# V4-AddOnESP32-V02-011.net
KiCad netlist of a schematic drawn in EAGLE
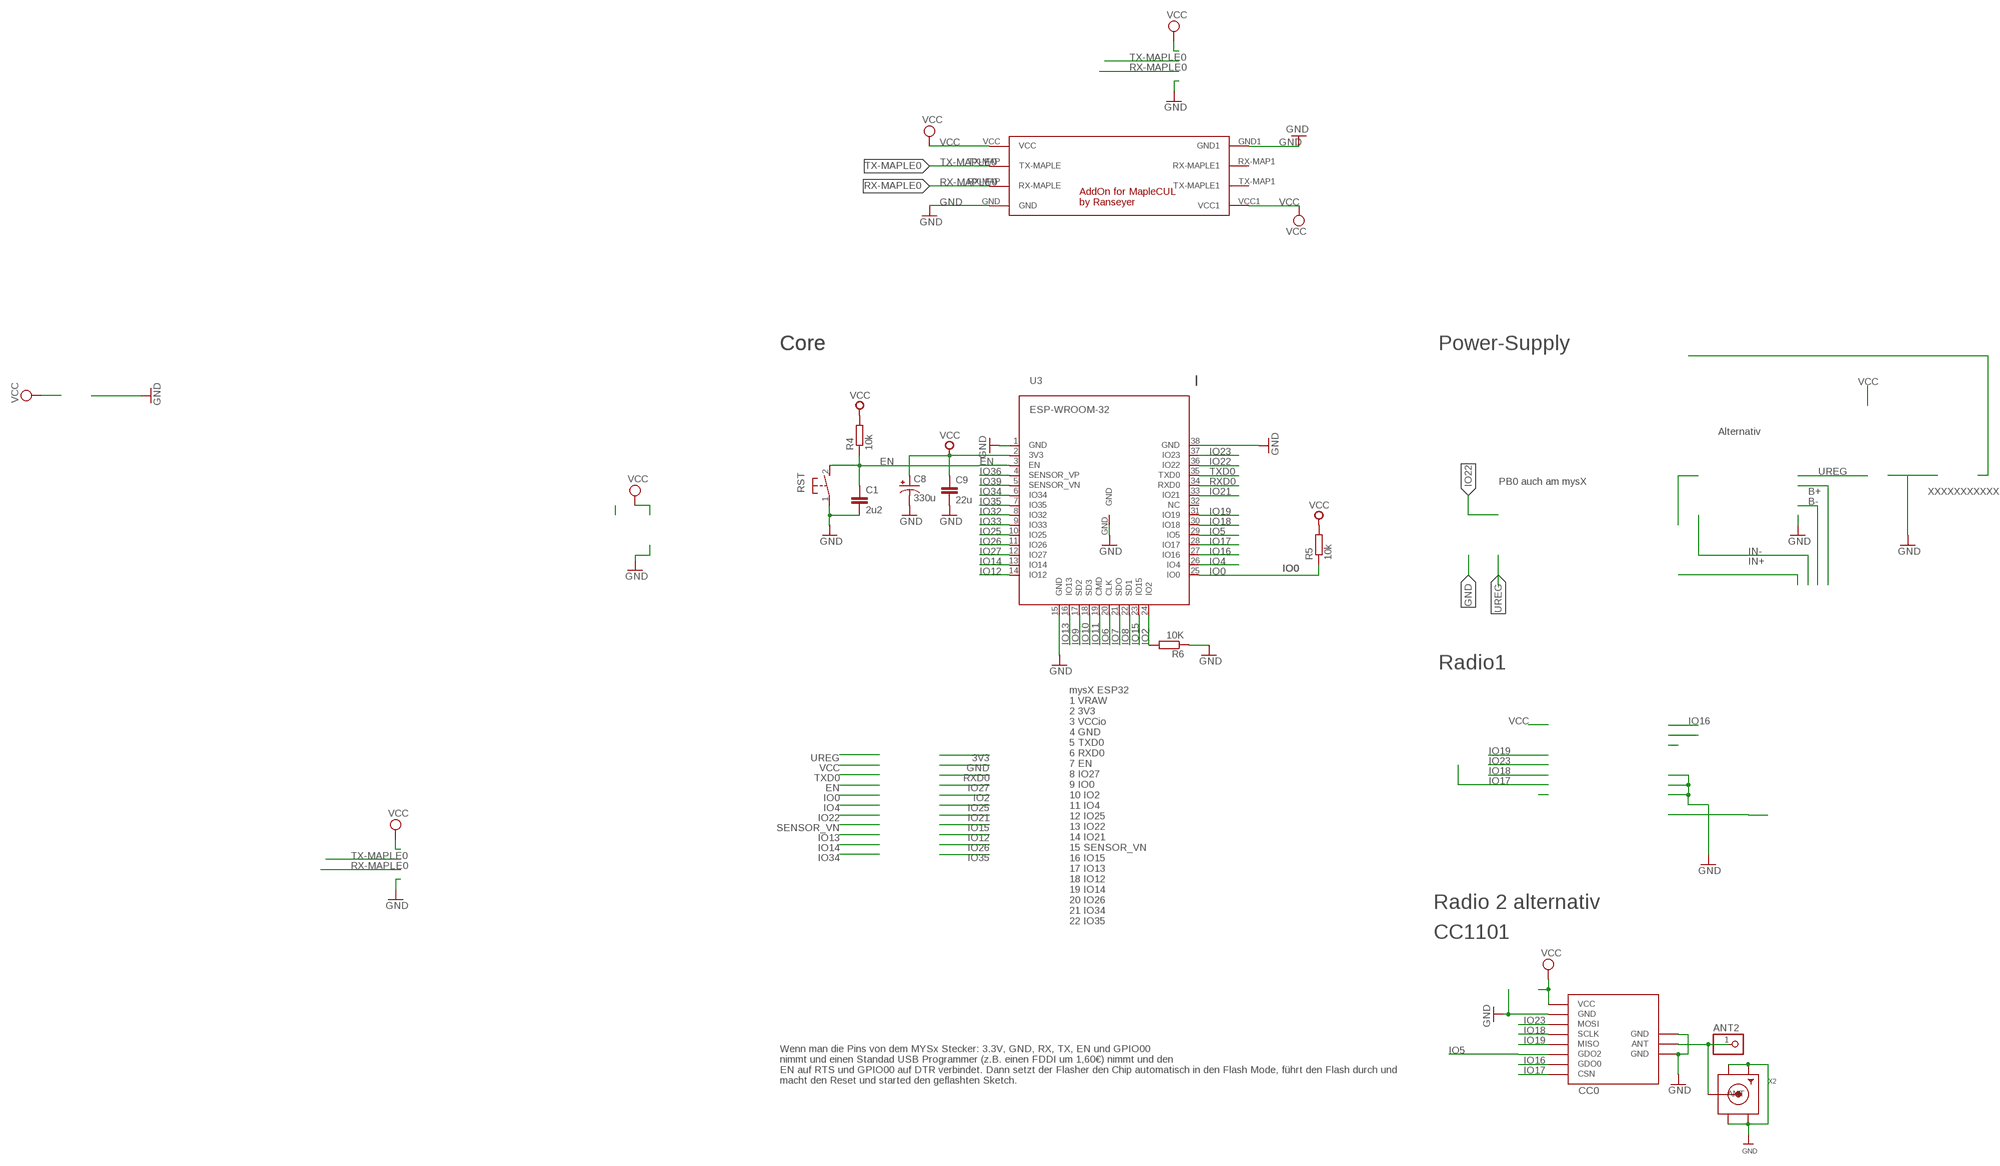
[diagram p0: schematic, sheet 1]

(export (version "E")
  (design (tool "Eeschema 10.0.6"))
  (components
    (comp (ref "ANT2")
      (value "PINHD-1X1")
      (footprint "eagle-import:1X01")
      (libsource (lib "eagle-import") (part "PINHD-1X1"))
    )
    (comp (ref "C1")
      (value "2u2")
      (footprint "eagle-import:C0805")
      (libsource (lib "eagle-import") (part "C-EUC0805"))
    )
    (comp (ref "C8")
      (value "330u")
      (footprint "eagle-import:VISHAY_C")
      (libsource (lib "eagle-import") (part "CAP_POLSMD"))
    )
    (comp (ref "C9")
      (value "22u")
      (footprint "eagle-import:C0805")
      (libsource (lib "eagle-import") (part "C-EUC0805"))
    )
    (comp (ref "CC0")
      (value "CC1101")
      (footprint "eagle-import:CC1101_MODULE1_SMD")
      (libsource (lib "eagle-import") (part "CC1101_MODULE1SMD"))
    )
    (comp (ref "R4")
      (value "10k")
      (footprint "eagle-import:M0805")
      (libsource (lib "eagle-import") (part "rcl@1_R-EU_M0805"))
    )
    (comp (ref "R5")
      (value "10k")
      (footprint "eagle-import:M0805")
      (libsource (lib "eagle-import") (part "rcl_334_R-EU_M0805"))
    )
    (comp (ref "R6")
      (value "10K")
      (footprint "eagle-import:M0805")
      (libsource (lib "eagle-import") (part "R-EU_M0805"))
    )
    (comp (ref "RST")
      (value "DTSM-3")
      (footprint "eagle-import:DTSM-3")
      (libsource (lib "eagle-import") (part "DTSM-3"))
    )
    (comp (ref "U$2")
      (value "MAPLE-CUL-ADDON-V01")
      (footprint "eagle-import:MAPLE-CUL-V01")
      (libsource (lib "eagle-import") (part "MAPLE-CUL-ADDON-V01"))
    )
    (comp (ref "U3")
      (value "ESP-WROOM-32")
      (footprint "eagle-import:ESP-WROOM-32")
      (libsource (lib "eagle-import") (part "ESP-WROOM-32"))
    )
    (comp (ref "X2")
      (value "SMACONNECTOR_EDGE")
      (footprint "eagle-import:SMA_EDGELAUNCH")
      (libsource (lib "eagle-import") (part "SMACONNECTOR_EDGE"))
    )
  )
  (nets
    (net (code "4") (name "/EN") (class "Default")
      (node (ref "C1") (pin "1") (pinfunction "1_1") (pintype "passive"))
      (node (ref "R4") (pin "1") (pinfunction "1_1") (pintype "passive"))
      (node (ref "RST") (pin "2") (pinfunction "2_2") (pintype "passive"))
      (node (ref "U3") (pin "3") (pinfunction "EN_3") (pintype "bidirectional"))
    )
    (net (code "7") (name "/IO0") (class "Default")
      (node (ref "R5") (pin "1") (pinfunction "1_1") (pintype "passive"))
      (node (ref "U3") (pin "25") (pinfunction "IO0_25") (pintype "bidirectional"))
    )
    (net (code "8") (name "/IO2") (class "Default")
      (node (ref "R6") (pin "2") (pinfunction "2_2") (pintype "passive"))
      (node (ref "U3") (pin "24") (pinfunction "IO2_24") (pintype "bidirectional"))
    )
    (net (code "9") (name "/IO4") (class "Default")
      (node (ref "U3") (pin "26") (pinfunction "IO4_26") (pintype "bidirectional"))
    )
    (net (code "10") (name "/IO5") (class "Default")
      (node (ref "CC0") (pin "GDO2") (pinfunction "GDO2_GDO2") (pintype "bidirectional"))
      (node (ref "U3") (pin "29") (pinfunction "IO5_29") (pintype "bidirectional"))
    )
    (net (code "11") (name "/IO6") (class "Default")
      (node (ref "U3") (pin "20") (pinfunction "CLK_20") (pintype "bidirectional"))
    )
    (net (code "12") (name "/IO7") (class "Default")
      (node (ref "U3") (pin "21") (pinfunction "SDO_21") (pintype "bidirectional"))
    )
    (net (code "13") (name "/IO8") (class "Default")
      (node (ref "U3") (pin "22") (pinfunction "SD1_22") (pintype "bidirectional"))
    )
    (net (code "14") (name "/IO9") (class "Default")
      (node (ref "U3") (pin "17") (pinfunction "SD2_17") (pintype "bidirectional"))
    )
    (net (code "15") (name "/IO10") (class "Default")
      (node (ref "U3") (pin "18") (pinfunction "SD3_18") (pintype "bidirectional"))
    )
    (net (code "16") (name "/IO11") (class "Default")
      (node (ref "U3") (pin "19") (pinfunction "CMD_19") (pintype "bidirectional"))
    )
    (net (code "17") (name "/IO12") (class "Default")
      (node (ref "U3") (pin "14") (pinfunction "IO12_14") (pintype "bidirectional"))
    )
    (net (code "18") (name "/IO13") (class "Default")
      (node (ref "U3") (pin "16") (pinfunction "IO13_16") (pintype "bidirectional"))
    )
    (net (code "19") (name "/IO14") (class "Default")
      (node (ref "U3") (pin "13") (pinfunction "IO14_13") (pintype "bidirectional"))
    )
    (net (code "20") (name "/IO15") (class "Default")
      (node (ref "U3") (pin "23") (pinfunction "IO15_23") (pintype "bidirectional"))
    )
    (net (code "21") (name "/IO16") (class "Default")
      (node (ref "CC0") (pin "GDO0") (pinfunction "GDO0_GDO0") (pintype "bidirectional"))
      (node (ref "U3") (pin "27") (pinfunction "IO16_27") (pintype "bidirectional"))
    )
    (net (code "22") (name "/IO17") (class "Default")
      (node (ref "CC0") (pin "CSN") (pinfunction "CSN_CSN") (pintype "bidirectional"))
      (node (ref "U3") (pin "28") (pinfunction "IO17_28") (pintype "bidirectional"))
    )
    (net (code "23") (name "/IO18") (class "Default")
      (node (ref "CC0") (pin "SCLK") (pinfunction "SCLK_SCLK") (pintype "bidirectional"))
      (node (ref "U3") (pin "30") (pinfunction "IO18_30") (pintype "bidirectional"))
    )
    (net (code "24") (name "/IO19") (class "Default")
      (node (ref "CC0") (pin "MISO") (pinfunction "MISO_MISO") (pintype "bidirectional"))
      (node (ref "U3") (pin "31") (pinfunction "IO19_31") (pintype "bidirectional"))
    )
    (net (code "25") (name "/IO21") (class "Default")
      (node (ref "U3") (pin "33") (pinfunction "IO21_33") (pintype "bidirectional"))
    )
    (net (code "26") (name "/IO23") (class "Default")
      (node (ref "CC0") (pin "MOSI") (pinfunction "MOSI_MOSI") (pintype "bidirectional"))
      (node (ref "U3") (pin "37") (pinfunction "IO23_37") (pintype "bidirectional"))
    )
    (net (code "27") (name "/IO25") (class "Default")
      (node (ref "U3") (pin "10") (pinfunction "IO25_10") (pintype "bidirectional"))
    )
    (net (code "28") (name "/IO26") (class "Default")
      (node (ref "U3") (pin "11") (pinfunction "IO26_11") (pintype "bidirectional"))
    )
    (net (code "29") (name "/IO27") (class "Default")
      (node (ref "U3") (pin "12") (pinfunction "IO27_12") (pintype "bidirectional"))
    )
    (net (code "30") (name "/IO32") (class "Default")
      (node (ref "U3") (pin "8") (pinfunction "IO32_8") (pintype "bidirectional"))
    )
    (net (code "31") (name "/IO33") (class "Default")
      (node (ref "U3") (pin "9") (pinfunction "IO33_9") (pintype "bidirectional"))
    )
    (net (code "32") (name "/IO34") (class "Default")
      (node (ref "U3") (pin "6") (pinfunction "IO34_6") (pintype "bidirectional"))
    )
    (net (code "33") (name "/IO35") (class "Default")
      (node (ref "U3") (pin "7") (pinfunction "IO35_7") (pintype "bidirectional"))
    )
    (net (code "34") (name "/IO36") (class "Default")
      (node (ref "U3") (pin "4") (pinfunction "SENSOR_VP_4") (pintype "bidirectional"))
    )
    (net (code "35") (name "/IO39") (class "Default")
      (node (ref "U3") (pin "5") (pinfunction "SENSOR_VN_5") (pintype "bidirectional"))
    )
    (net (code "36") (name "/RXD0") (class "Default")
      (node (ref "U3") (pin "34") (pinfunction "RXD0_34") (pintype "bidirectional"))
    )
    (net (code "38") (name "/TXD0") (class "Default")
      (node (ref "U3") (pin "35") (pinfunction "TXD0_35") (pintype "bidirectional"))
    )
    (net (code "39") (name "GND") (class "Default")
      (node (ref "C1") (pin "2") (pinfunction "2_2") (pintype "passive"))
      (node (ref "C8") (pin "-") (pinfunction "-_-") (pintype "passive"))
      (node (ref "C9") (pin "2") (pinfunction "2_2") (pintype "passive"))
      (node (ref "CC0") (pin "GND@0") (pinfunction "GND_GND@0") (pintype "power_in"))
      (node (ref "CC0") (pin "GND@1") (pinfunction "GND_GND@1") (pintype "power_in"))
      (node (ref "CC0") (pin "GND@2") (pinfunction "GND_GND@2") (pintype "power_in"))
      (node (ref "R6") (pin "1") (pinfunction "1_1") (pintype "passive"))
      (node (ref "RST") (pin "1") (pinfunction "1_1") (pintype "passive"))
      (node (ref "U$2") (pin "GND") (pinfunction "GND_GND") (pintype "bidirectional"))
      (node (ref "U$2") (pin "GND1") (pinfunction "GND1_GND1") (pintype "bidirectional"))
      (node (ref "U3") (pin "1") (pinfunction "GND_1") (pintype "bidirectional"))
      (node (ref "U3") (pin "15") (pinfunction "GND_15") (pintype "bidirectional"))
      (node (ref "U3") (pin "38") (pinfunction "GND_38") (pintype "bidirectional"))
      (node (ref "U3") (pin "GND") (pinfunction "GND_GND") (pintype "bidirectional"))
      (node (ref "X2") (pin "GND@1") (pinfunction "GND4_GND@1") (pintype "power_in"))
      (node (ref "X2") (pin "GND@2") (pinfunction "GND3_GND@2") (pintype "power_in"))
      (node (ref "X2") (pin "GND@3") (pinfunction "GND2_GND@3") (pintype "power_in"))
      (node (ref "X2") (pin "GND@4") (pinfunction "GND1_GND@4") (pintype "power_in"))
    )
    (net (code "40") (name "IO22") (class "Default")
      (node (ref "U3") (pin "36") (pinfunction "IO22_36") (pintype "bidirectional"))
    )
    (net (code "41") (name "Net-(X2-ANT)") (class "Default")
      (node (ref "ANT2") (pin "1") (pinfunction "1_1") (pintype "passive"))
      (node (ref "CC0") (pin "ANT") (pinfunction "ANT_ANT") (pintype "output"))
      (node (ref "X2") (pin "P") (pinfunction "ANT_P") (pintype "bidirectional"))
    )
    (net (code "42") (name "RX-MAPLE0") (class "Default")
      (node (ref "U$2") (pin "RX-MAP") (pinfunction "RX-MAPLE_RX-MAP") (pintype "bidirectional"))
    )
    (net (code "43") (name "TX-MAPLE0") (class "Default")
      (node (ref "U$2") (pin "TX-MAP") (pinfunction "TX-MAPLE_TX-MAP") (pintype "bidirectional"))
    )
    (net (code "45") (name "VCC") (class "Default")
      (node (ref "C8") (pin "+") (pinfunction "+_+") (pintype "passive"))
      (node (ref "C9") (pin "1") (pinfunction "1_1") (pintype "passive"))
      (node (ref "CC0") (pin "VCC") (pinfunction "VCC_VCC") (pintype "power_in"))
      (node (ref "R4") (pin "2") (pinfunction "2_2") (pintype "passive"))
      (node (ref "R5") (pin "2") (pinfunction "2_2") (pintype "passive"))
      (node (ref "U$2") (pin "VCC") (pinfunction "VCC_VCC") (pintype "bidirectional"))
      (node (ref "U$2") (pin "VCC1") (pinfunction "VCC1_VCC1") (pintype "bidirectional"))
      (node (ref "U3") (pin "2") (pinfunction "3V3_2") (pintype "bidirectional"))
    )
    (net (code "46") (name "unconnected-(U$2-RX-MAPLE1-PadRX-MAP1)") (class "Default")
      (node (ref "U$2") (pin "RX-MAP1") (pinfunction "RX-MAPLE1_RX-MAP1") (pintype "bidirectional"))
    )
    (net (code "47") (name "unconnected-(U$2-TX-MAPLE1-PadTX-MAP1)") (class "Default")
      (node (ref "U$2") (pin "TX-MAP1") (pinfunction "TX-MAPLE1_TX-MAP1") (pintype "bidirectional"))
    )
    (net (code "48") (name "unconnected-(U3-NC-Pad32)") (class "Default")
      (node (ref "U3") (pin "32") (pinfunction "NC_32") (pintype "bidirectional"))
    )
  )
)
